# emonDCduo_v0_1.net
KiCad netlist of a schematic drawn in EAGLE
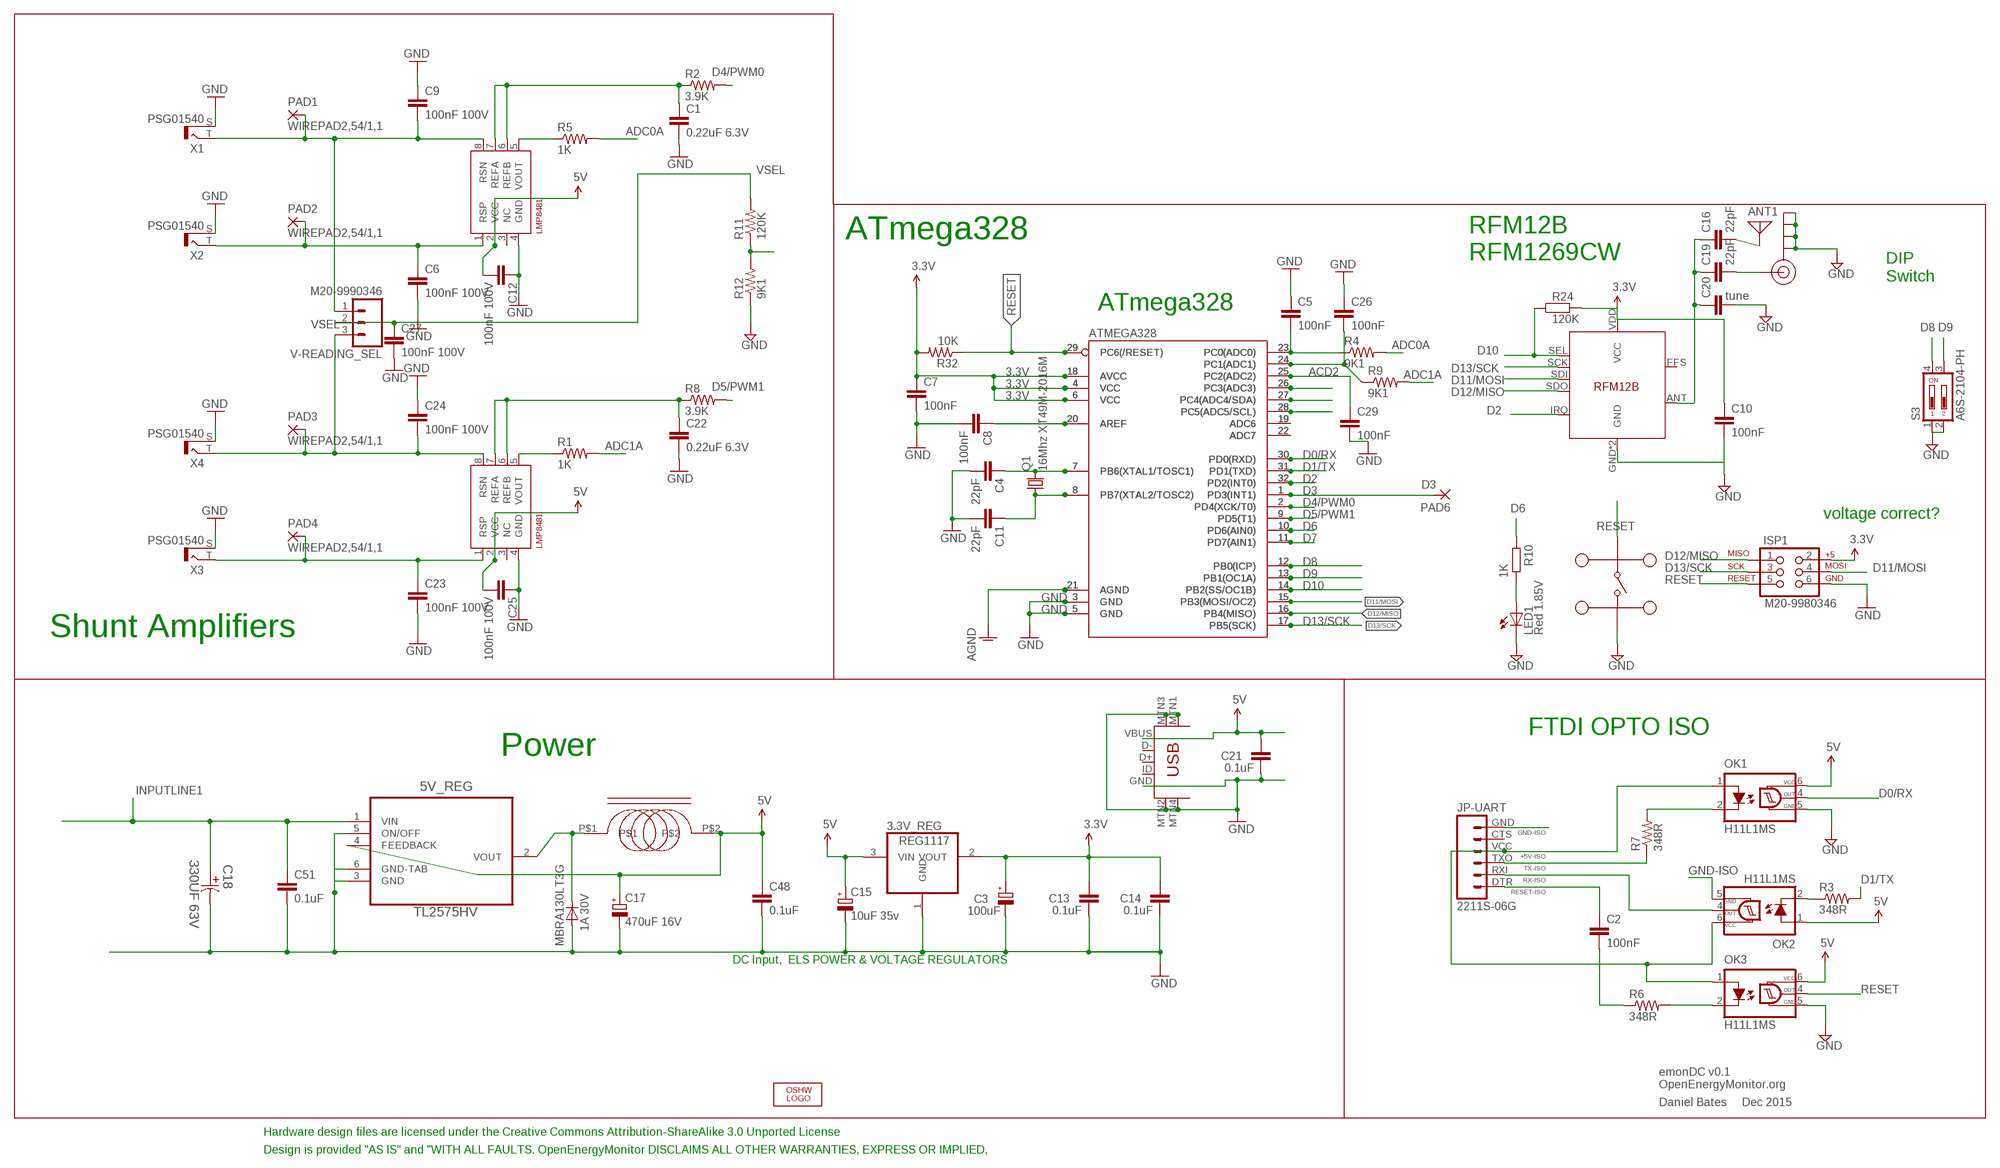
[diagram p0: schematic, sheet 1]

(export (version "E")
  (design (tool "Eeschema 10.0.6"))
  (components
    (comp (ref "3.3V_REG")
      (value "REG1117")
      (footprint "eagle-import:SOT223")
      (fields (field (name "MF") "TEXAS INSTRUMENTS"))
      (libsource (lib "eagle-import") (part "REG1117"))
    )
    (comp (ref "5V_REG")
      (value "TL2575HV")
      (footprint "eagle-import:TO-263")
      (fields (field (name "MF") "TEXAS INSTRUMENTS") (field (name "MPN") "LM2575HVS-15/NOPB"))
      (libsource (lib "eagle-import") (part "TL2575HV-05IKTTR"))
    )
    (comp (ref "ANT1")
      (value "ANTENNA")
      (footprint "eagle-import:PAD-01")
      (libsource (lib "eagle-import") (part "ANTENNA"))
    )
    (comp (ref "ATMEGA328")
      (value "ATMEGA168MLF")
      (footprint "eagle-import:MLF32")
      (fields (field (name "MF") "ATMEL") (field (name "MPN") "ATMEGA168-20MU"))
      (libsource (lib "eagle-import") (part "ATMEGA168MLF"))
    )
    (comp (ref "C1")
      (value "0.22uF 6.3V")
      (footprint "eagle-import:C0402K")
      (fields (field (name "MF") "AVX") (field (name "MPN") "04026D224KAT2A"))
      (libsource (lib "eagle-import") (part "C-EUC0402K"))
    )
    (comp (ref "C2")
      (value "100nF")
      (footprint "eagle-import:C0402K")
      (fields (field (name "MF") "WALSIN") (field (name "MPN") "0402X104K100CT"))
      (libsource (lib "eagle-import") (part "C-EUC0402K"))
    )
    (comp (ref "C3")
      (value "100uF")
      (footprint "eagle-import:153CLV-0605")
      (fields (field (name "MF") "NICHICON") (field (name "MPN") "UWX0J101MCL1GB"))
      (libsource (lib "eagle-import") (part "resistor_CPOL-EU153CLV-0605"))
    )
    (comp (ref "C4")
      (value "22pF")
      (footprint "eagle-import:C0603")
      (fields (field (name "MF") "YAGEO (PHYCOMP)") (field (name "MPN") "CC0402JRNPO9BN470"))
      (libsource (lib "eagle-import") (part "resistor_C-EUC0603"))
    )
    (comp (ref "C5")
      (value "100nF")
      (footprint "eagle-import:C0402K")
      (fields (field (name "MF") "WALSIN") (field (name "MPN") "0402X104K100CT"))
      (libsource (lib "eagle-import") (part "C-EUC0402K"))
    )
    (comp (ref "C6")
      (value "100nF 100V")
      (footprint "eagle-import:C0805K")
      (fields (field (name "MF") "AVX") (field (name "MPN") "08051C104K4Z2A"))
      (libsource (lib "eagle-import") (part "C-EUC0805K"))
    )
    (comp (ref "C7")
      (value "100nF")
      (footprint "eagle-import:C0402K")
      (fields (field (name "MF") "WALSIN") (field (name "MPN") "0402X104K100CT"))
      (libsource (lib "eagle-import") (part "C-EUC0402K"))
    )
    (comp (ref "C8")
      (value "100nF")
      (footprint "eagle-import:C0402K")
      (fields (field (name "MF") "WALSIN") (field (name "MPN") "0402X104K100CT"))
      (libsource (lib "eagle-import") (part "C-EUC0402K"))
    )
    (comp (ref "C9")
      (value "100nF 100V")
      (footprint "eagle-import:C0805K")
      (fields (field (name "MF") "AVX") (field (name "MPN") "08051C104K4Z2A"))
      (libsource (lib "eagle-import") (part "C-EUC0805K"))
    )
    (comp (ref "C10")
      (value "100nF")
      (footprint "eagle-import:C0402K")
      (fields (field (name "MF") "WALSIN") (field (name "MPN") "0402X104K100CT"))
      (libsource (lib "eagle-import") (part "C-EUC0402K"))
    )
    (comp (ref "C11")
      (value "22pF")
      (footprint "eagle-import:C0603")
      (fields (field (name "MF") "YAGEO (PHYCOMP)") (field (name "MPN") "CC0402JRNPO9BN470"))
      (libsource (lib "eagle-import") (part "resistor_C-EUC0603"))
    )
    (comp (ref "C12")
      (value "100nF 100V")
      (footprint "eagle-import:C0805K")
      (fields (field (name "MF") "AVX") (field (name "MPN") "08051C104K4Z2A"))
      (libsource (lib "eagle-import") (part "C-EUC0805K"))
    )
    (comp (ref "C13")
      (value "0.1uF")
      (footprint "eagle-import:C0805K")
      (fields (field (name "MF") "WALSIN") (field (name "MPN") "0805B104K160CT"))
      (libsource (lib "eagle-import") (part "C-EUC0805K"))
    )
    (comp (ref "C14")
      (value "0.1uF")
      (footprint "eagle-import:C0805K")
      (fields (field (name "MF") "WALSIN") (field (name "MPN") "0805B104K160CT"))
      (libsource (lib "eagle-import") (part "C-EUC0805K"))
    )
    (comp (ref "C15")
      (value "10uF 35v")
      (footprint "eagle-import:E1,8-4")
      (fields (field (name "MF") "AVX") (field (name "MPN") "TAJD106K035RNJ"))
      (libsource (lib "eagle-import") (part "CPOL-EUE1.8-4"))
    )
    (comp (ref "C16")
      (value "22pF")
      (footprint "eagle-import:C0603")
      (fields (field (name "MF") "YAGEO (PHYCOMP)") (field (name "MPN") "CC0402JRNPO9BN470"))
      (libsource (lib "eagle-import") (part "C-EUC0603"))
    )
    (comp (ref "C17")
      (value "470uF 16V")
      (footprint "eagle-import:E3,5-8")
      (fields (field (name "MF") "RUBYCON") (field (name "MPN") "16YXF470MEFC10X12.5"))
      (libsource (lib "eagle-import") (part "CPOL-EUE3.5-8"))
    )
    (comp (ref "C18")
      (value "330UF 63V")
      (footprint "eagle-import:CAPPR500-1000X2000")
      (fields
        (field (name "MPN") "ECA1JHG331")
        (field (name "TOLERANCE") "±20 %")
        (field (name "MF") "PANASONIC ELECTRONIC COMPONENTS")
        (field (name "OC_FARNELL") "unknown")
      )
      (libsource (lib "eagle-import") (part "ECA-D10XP51JHG331"))
    )
    (comp (ref "C19")
      (value "22pF")
      (footprint "eagle-import:C0603")
      (fields (field (name "MF") "YAGEO (PHYCOMP)") (field (name "MPN") "CC0402JRNPO9BN470"))
      (libsource (lib "eagle-import") (part "C-EUC0603"))
    )
    (comp (ref "C20")
      (value "tune")
      (footprint "eagle-import:C0603")
      (libsource (lib "eagle-import") (part "C-EUC0603"))
    )
    (comp (ref "C21")
      (value "0.1uF")
      (footprint "eagle-import:C0805K")
      (fields (field (name "MF") "WALSIN") (field (name "MPN") "0805B104K160CT"))
      (libsource (lib "eagle-import") (part "C-EUC0805K"))
    )
    (comp (ref "C22")
      (value "0.22uF 6.3V")
      (footprint "eagle-import:C0402K")
      (fields (field (name "MF") "AVX") (field (name "MPN") "04026D224KAT2A"))
      (libsource (lib "eagle-import") (part "C-EUC0402K"))
    )
    (comp (ref "C23")
      (value "100nF 100V")
      (footprint "eagle-import:C0805K")
      (fields (field (name "MF") "AVX") (field (name "MPN") "08051C104K4Z2A"))
      (libsource (lib "eagle-import") (part "C-EUC0805K"))
    )
    (comp (ref "C24")
      (value "100nF 100V")
      (footprint "eagle-import:C0805K")
      (fields (field (name "MF") "AVX") (field (name "MPN") "08051C104K4Z2A"))
      (libsource (lib "eagle-import") (part "C-EUC0805K"))
    )
    (comp (ref "C25")
      (value "100nF 100V")
      (footprint "eagle-import:C0805K")
      (fields (field (name "MF") "AVX") (field (name "MPN") "08051C104K4Z2A"))
      (libsource (lib "eagle-import") (part "C-EUC0805K"))
    )
    (comp (ref "C26")
      (value "100nF")
      (footprint "eagle-import:C0402K")
      (fields (field (name "MF") "WALSIN") (field (name "MPN") "0402X104K100CT"))
      (libsource (lib "eagle-import") (part "C-EUC0402K"))
    )
    (comp (ref "C27")
      (value "100nF 100V")
      (footprint "eagle-import:C0805K")
      (fields (field (name "MF") "AVX") (field (name "MPN") "08051C104K4Z2A"))
      (libsource (lib "eagle-import") (part "C-EUC0805K"))
    )
    (comp (ref "C29")
      (value "100nF")
      (footprint "eagle-import:C0402K")
      (fields (field (name "MF") "WALSIN") (field (name "MPN") "0402X104K100CT"))
      (libsource (lib "eagle-import") (part "C-EUC0402K"))
    )
    (comp (ref "C48")
      (value "0.1uF")
      (footprint "eagle-import:C0805K")
      (fields (field (name "MF") "WALSIN") (field (name "MPN") "0805B104K160CT"))
      (libsource (lib "eagle-import") (part "C-EUC0805K"))
    )
    (comp (ref "C51")
      (value "0.1uF")
      (footprint "eagle-import:C0805")
      (fields (field (name "MF") "WALSIN") (field (name "MPN") "0805B104K160CT"))
      (libsource (lib "eagle-import") (part "resistor_C-EUC0805"))
    )
    (comp (ref "D2")
      (value "MBRA130LT3G")
      (footprint "eagle-import:DO-214")
      (fields (field (name "MF") "ON SEMICONDUCTOR"))
      (libsource (lib "eagle-import") (part "MBRA130LT3G"))
    )
    (comp (ref "I1")
      (value "SRR0603-331KL")
      (footprint "eagle-import:SRR0603-331KL")
      (fields (field (name "MF") "BOURNS"))
      (libsource (lib "eagle-import") (part "SRR0603-331KL"))
    )
    (comp (ref "ISP1")
      (value "M20-9980346")
      (footprint "eagle-import:2X3")
      (fields (field (name "MF") "HARWIN"))
      (libsource (lib "eagle-import") (part "AVR_SPI_PRG_6PTH"))
    )
    (comp (ref "J$1")
      (value "SMA_EDGE")
      (footprint "eagle-import:SMA-EDGE")
      (libsource (lib "eagle-import") (part "SMA_EDGE"))
    )
    (comp (ref "JP-UART")
      (value "2211S-06G")
      (footprint "eagle-import:FTDI_BASIC")
      (fields (field (name "MF") "MULTICOMP"))
      (libsource (lib "eagle-import") (part "FTDI_BASICPTH"))
    )
    (comp (ref "LED1")
      (value "Red 1.85V")
      (footprint "eagle-import:CHIP-LED0805")
      (fields (field (name "MF") "ROHM") (field (name "MPN") "SML-211UTT86K"))
      (libsource (lib "eagle-import") (part "LEDCHIP-LED0805"))
    )
    (comp (ref "LMP2")
      (value "LMP8481SMCLMP8481")
      (footprint "eagle-import:S-PDSO-G08")
      (fields (field (name "MF") "TEXAS INSTRUMENTS") (field (name "MPN") "LMP8481MME-S/NOPB"))
      (libsource (lib "eagle-import") (part "LMP8481SMCLMP8481"))
    )
    (comp (ref "LMP8481")
      (value "LMP8481SMCLMP8481")
      (footprint "eagle-import:S-PDSO-G08")
      (fields (field (name "MF") "TEXAS INSTRUMENTS") (field (name "MPN") "LMP8481MME-S/NOPB"))
      (libsource (lib "eagle-import") (part "LMP8481SMCLMP8481"))
    )
    (comp (ref "LOGO1")
      (value "OSHW_LOGO_6MILX0200-NT")
      (footprint "eagle-import:OSHW_6X200_NOTEXT")
      (libsource (lib "eagle-import") (part "OSHW_LOGO_6MILX0200-NT"))
    )
    (comp (ref "OK1")
      (value "H11L1MS")
      (footprint "eagle-import:DIL6-SMD")
      (libsource (lib "eagle-import") (part "H11LMS1"))
    )
    (comp (ref "OK2")
      (value "H11L1MS")
      (footprint "eagle-import:DIL6-SMD")
      (libsource (lib "eagle-import") (part "H11LMS1"))
    )
    (comp (ref "OK3")
      (value "H11L1MS")
      (footprint "eagle-import:DIL6-SMD")
      (libsource (lib "eagle-import") (part "H11LMS1"))
    )
    (comp (ref "PAD1")
      (value "WIREPAD2,54/1,1")
      (footprint "eagle-import:2,54_1,1")
      (libsource (lib "eagle-import") (part "WIREPAD2,54/1,1"))
    )
    (comp (ref "PAD2")
      (value "WIREPAD2,54/1,1")
      (footprint "eagle-import:2,54_1,1")
      (libsource (lib "eagle-import") (part "WIREPAD2,54/1,1"))
    )
    (comp (ref "PAD3")
      (value "WIREPAD2,54/1,1")
      (footprint "eagle-import:2,54_1,1")
      (libsource (lib "eagle-import") (part "WIREPAD2,54/1,1"))
    )
    (comp (ref "PAD4")
      (value "WIREPAD2,54/1,1")
      (footprint "eagle-import:2,54_1,1")
      (libsource (lib "eagle-import") (part "WIREPAD2,54/1,1"))
    )
    (comp (ref "PAD6")
      (value "WIREPAD2,54/1,1")
      (footprint "eagle-import:2,54_1,1")
      (libsource (lib "eagle-import") (part "WIREPAD2,54/1,1"))
    )
    (comp (ref "Q1")
      (value "16Mhz XT49M-2016M")
      (footprint "eagle-import:HC49UP")
      (fields
        (field (name "MF") "VISHAY")
        (field (name "MPN") "XT49M-2016M")
        (field (name "OC_FARNELL") "1469641")
      )
      (libsource (lib "eagle-import") (part "CRYSTALHC49UP"))
    )
    (comp (ref "R1")
      (value "1K")
      (footprint "eagle-import:R0603")
      (fields (field (name "MF") "MULTICOMP") (field (name "MPN") "MC0063W060351K"))
      (libsource (lib "eagle-import") (part "R-US_R0603"))
    )
    (comp (ref "R2")
      (value "3.9K")
      (footprint "eagle-import:R0603")
      (fields (field (name "MF") "VISHAY") (field (name "MPN") "CRCW06039K09FKEA"))
      (libsource (lib "eagle-import") (part "R-US_R0603"))
    )
    (comp (ref "R3")
      (value "348R")
      (footprint "eagle-import:R0603")
      (fields (field (name "MF") "MULTICOMP") (field (name "MPN") "MC0063W06031348R"))
      (libsource (lib "eagle-import") (part "R-US_R0603"))
    )
    (comp (ref "R4")
      (value "9K1")
      (footprint "eagle-import:R0603")
      (fields (field (name "MF") "MULTICOMP") (field (name "MPN") "MC01W080559K1"))
      (libsource (lib "eagle-import") (part "R-US_R0603"))
    )
    (comp (ref "R5")
      (value "1K")
      (footprint "eagle-import:R0603")
      (fields (field (name "MF") "MULTICOMP") (field (name "MPN") "MC0063W060351K"))
      (libsource (lib "eagle-import") (part "R-US_R0603"))
    )
    (comp (ref "R6")
      (value "348R")
      (footprint "eagle-import:R0603")
      (fields (field (name "MF") "MULTICOMP") (field (name "MPN") "MC0063W06031348R"))
      (libsource (lib "eagle-import") (part "R-US_R0603"))
    )
    (comp (ref "R7")
      (value "348R")
      (footprint "eagle-import:R0603")
      (fields (field (name "MF") "MULTICOMP") (field (name "MPN") "MC0063W06031348R"))
      (libsource (lib "eagle-import") (part "R-US_R0603"))
    )
    (comp (ref "R8")
      (value "3.9K")
      (footprint "eagle-import:R0603")
      (fields (field (name "MF") "VISHAY") (field (name "MPN") "CRCW06039K09FKEA"))
      (libsource (lib "eagle-import") (part "R-US_R0603"))
    )
    (comp (ref "R9")
      (value "9K1")
      (footprint "eagle-import:R0603")
      (fields (field (name "MF") "MULTICOMP") (field (name "MPN") "MC01W080559K1"))
      (libsource (lib "eagle-import") (part "R-US_R0603"))
    )
    (comp (ref "R10")
      (value "1K")
      (footprint "eagle-import:R0603")
      (fields (field (name "MF") "MULTICOMP") (field (name "MPN") "MC0063W060351K"))
      (libsource (lib "eagle-import") (part "R-EU_R0603"))
    )
    (comp (ref "R11")
      (value "120K")
      (footprint "eagle-import:R0603")
      (fields (field (name "MF") "MULTICOMP") (field (name "MPN") "MC01W080559K1"))
      (libsource (lib "eagle-import") (part "R-US_R0603"))
    )
    (comp (ref "R12")
      (value "9K1")
      (footprint "eagle-import:R0603")
      (fields (field (name "MF") "MULTICOMP") (field (name "MPN") "MC01W080559K1"))
      (libsource (lib "eagle-import") (part "R-US_R0603"))
    )
    (comp (ref "R24")
      (value "120K")
      (footprint "eagle-import:R0603")
      (fields (field (name "MF") "YAGEO (PHYCOMP)") (field (name "MPN") "RC0603FR-07120KL"))
      (libsource (lib "eagle-import") (part "R-EU_R0603"))
    )
    (comp (ref "R32")
      (value "10K")
      (footprint "eagle-import:R0603")
      (fields (field (name "MF") "MULTICOMP") (field (name "MPN") "MC0063W0603510K"))
      (libsource (lib "eagle-import") (part "R-US_R0603"))
    )
    (comp (ref "RF")
      (value "RFM12B")
      (footprint "eagle-import:RFM12B")
      (libsource (lib "eagle-import") (part "RFM12B"))
    )
    (comp (ref "S3")
      (value "A6S-2104-PH")
      (footprint "eagle-import:DIP_SWITCH_SMT")
      (fields (field (name "MF") "OMRON ELECTRONIC COMPONENTS") (field (name "MPN") "A6S2104H"))
      (libsource (lib "eagle-import") (part "2_SMT_DIP_SWITCH"))
    )
    (comp (ref "U$1")
      (value "MC32882")
      (footprint "eagle-import:SWITCH_TACT_MULTICOMP")
      (libsource (lib "eagle-import") (part "MC32882"))
    )
    (comp (ref "U1_TQFP")
      (value "ATMEGA328P")
      (footprint "eagle-import:TQFP32-08")
      (fields (field (name "MF") "ATMEL") (field (name "MPN") "ATMEGA328-AU"))
      (libsource (lib "eagle-import") (part "ATMEGA328_SMT"))
    )
    (comp (ref "USB")
      (value "MUSB-05-S-B-SM-A")
      (footprint "eagle-import:USB-MINIB-CISECO")
      (fields (field (name "MF") "MOLEX") (field (name "MPN") "67503-1020"))
      (libsource (lib "eagle-import") (part "USB-MINIB-5PIN"))
    )
    (comp (ref "V-READING_SEL")
      (value "M20-9990346")
      (footprint "eagle-import:1X03_SMD_RA_FEMALE_NOWRITE")
      (fields (field (name "MF") "HARWIN"))
      (libsource (lib "eagle-import") (part "M03SMD_RA_FEMALE_NOWRITE"))
    )
    (comp (ref "X1")
      (value "PSG01540")
      (footprint "eagle-import:WBTOR1")
      (fields
        (field (name "MPN") "WBTOR 1 BLACK")
        (field (name "MF") "PRO SIGNAL")
        (field (name "MPN_1") "PSG01540")
        (field (name "OC_FARNELL") "1280698")
      )
      (libsource (lib "eagle-import") (part "WBTOR1"))
    )
    (comp (ref "X2")
      (value "PSG01540")
      (footprint "eagle-import:WBTOR1")
      (fields
        (field (name "MPN") "WBTOR 1 BLACK")
        (field (name "MF") "PRO SIGNAL")
        (field (name "MPN_1") "PSG01540")
        (field (name "OC_FARNELL") "1280698")
      )
      (libsource (lib "eagle-import") (part "WBTOR1"))
    )
    (comp (ref "X3")
      (value "PSG01540")
      (footprint "eagle-import:WBTOR1")
      (fields
        (field (name "MPN") "WBTOR 1 BLACK")
        (field (name "MF") "PRO SIGNAL")
        (field (name "MPN_1") "PSG01540")
        (field (name "OC_FARNELL") "1280698")
      )
      (libsource (lib "eagle-import") (part "WBTOR1"))
    )
    (comp (ref "X4")
      (value "PSG01540")
      (footprint "eagle-import:WBTOR1")
      (fields
        (field (name "MPN") "WBTOR 1 BLACK")
        (field (name "MF") "PRO SIGNAL")
        (field (name "MPN_1") "PSG01540")
        (field (name "OC_FARNELL") "1280698")
      )
      (libsource (lib "eagle-import") (part "WBTOR1"))
    )
  )
  (nets
    (net (code "1") (name "/+5V-ISO") (class "Default")
      (node (ref "JP-UART") (pin "VCC") (pinfunction "4_VCC") (pintype "passive"))
      (node (ref "OK1") (pin "1") (pinfunction "A_1") (pintype "passive"))
      (node (ref "OK2") (pin "6") (pinfunction "VCC_6") (pintype "power_in"))
      (node (ref "OK3") (pin "1") (pinfunction "A_1") (pintype "passive"))
    )
    (net (code "2") (name "/ACD2") (class "Default")
      (node (ref "ATMEGA328") (pin "25") (pinfunction "PC2(ADC2)_25") (pintype "bidirectional"))
      (node (ref "C29") (pin "1") (pinfunction "1_1") (pintype "passive"))
      (node (ref "R11") (pin "1") (pinfunction "1_1") (pintype "passive"))
      (node (ref "R12") (pin "2") (pinfunction "2_2") (pintype "passive"))
      (node (ref "U1_TQFP") (pin "25") (pinfunction "PC2(ADC2)_25") (pintype "bidirectional"))
    )
    (net (code "3") (name "/ADC0A") (class "Default")
      (node (ref "R4") (pin "2") (pinfunction "2_2") (pintype "passive"))
      (node (ref "R5") (pin "2") (pinfunction "2_2") (pintype "passive"))
    )
    (net (code "4") (name "/ADC1A") (class "Default")
      (node (ref "R1") (pin "2") (pinfunction "2_2") (pintype "passive"))
      (node (ref "R9") (pin "2") (pinfunction "2_2") (pintype "passive"))
    )
    (net (code "5") (name "/D0{slash}RX") (class "Default")
      (node (ref "ATMEGA328") (pin "30") (pinfunction "PD0(RXD)_30") (pintype "bidirectional"))
      (node (ref "OK1") (pin "4") (pinfunction "OUT_4") (pintype "output"))
      (node (ref "U1_TQFP") (pin "30") (pinfunction "PD0(RXD)_30") (pintype "bidirectional"))
    )
    (net (code "6") (name "/D1{slash}TX") (class "Default")
      (node (ref "ATMEGA328") (pin "31") (pinfunction "PD1(TXD)_31") (pintype "bidirectional"))
      (node (ref "R3") (pin "2") (pinfunction "2_2") (pintype "passive"))
      (node (ref "U1_TQFP") (pin "31") (pinfunction "PD1(TXD)_31") (pintype "bidirectional"))
    )
    (net (code "7") (name "/D2") (class "Default")
      (node (ref "ATMEGA328") (pin "32") (pinfunction "PD2(INT0)_32") (pintype "bidirectional"))
      (node (ref "RF") (pin "IRQ") (pinfunction "IRQ_IRQ") (pintype "open_collector"))
      (node (ref "U1_TQFP") (pin "32") (pinfunction "PD2(INT0)_32") (pintype "bidirectional"))
    )
    (net (code "8") (name "/D3") (class "Default")
      (node (ref "ATMEGA328") (pin "1") (pinfunction "PD3(INT1)_1") (pintype "bidirectional"))
      (node (ref "PAD6") (pin "1") (pinfunction "P_1") (pintype "passive"))
      (node (ref "U1_TQFP") (pin "1") (pinfunction "PD3(INT1)_1") (pintype "bidirectional"))
    )
    (net (code "9") (name "/D4{slash}PWM0") (class "Default")
      (node (ref "ATMEGA328") (pin "2") (pinfunction "PD4(XCK/T0)_2") (pintype "bidirectional"))
      (node (ref "R2") (pin "2") (pinfunction "2_2") (pintype "passive"))
      (node (ref "U1_TQFP") (pin "2") (pinfunction "PD4(XCK/T0)_2") (pintype "bidirectional"))
    )
    (net (code "10") (name "/D5{slash}PWM1") (class "Default")
      (node (ref "ATMEGA328") (pin "9") (pinfunction "PD5(T1)_9") (pintype "bidirectional"))
      (node (ref "R8") (pin "2") (pinfunction "2_2") (pintype "passive"))
      (node (ref "U1_TQFP") (pin "9") (pinfunction "PD5(T1)_9") (pintype "bidirectional"))
    )
    (net (code "11") (name "/D6") (class "Default")
      (node (ref "ATMEGA328") (pin "10") (pinfunction "PD6(AIN0)_10") (pintype "bidirectional"))
      (node (ref "R10") (pin "2") (pinfunction "2_2") (pintype "passive"))
      (node (ref "U1_TQFP") (pin "10") (pinfunction "PD6(AIN0)_10") (pintype "bidirectional"))
    )
    (net (code "12") (name "/D7") (class "Default")
      (node (ref "ATMEGA328") (pin "11") (pinfunction "PD7(AIN1)_11") (pintype "bidirectional"))
      (node (ref "U1_TQFP") (pin "11") (pinfunction "PD7(AIN1)_11") (pintype "bidirectional"))
    )
    (net (code "13") (name "/D8") (class "Default")
      (node (ref "ATMEGA328") (pin "12") (pinfunction "PB0(ICP)_12") (pintype "bidirectional"))
      (node (ref "S3") (pin "4") (pinfunction "4_4") (pintype "passive"))
      (node (ref "U1_TQFP") (pin "12") (pinfunction "PB0(ICP)_12") (pintype "bidirectional"))
    )
    (net (code "14") (name "/D9") (class "Default")
      (node (ref "ATMEGA328") (pin "13") (pinfunction "PB1(OC1A)_13") (pintype "bidirectional"))
      (node (ref "S3") (pin "3") (pinfunction "3_3") (pintype "passive"))
      (node (ref "U1_TQFP") (pin "13") (pinfunction "PB1(OC1A)_13") (pintype "bidirectional"))
    )
    (net (code "15") (name "/D10") (class "Default")
      (node (ref "ATMEGA328") (pin "14") (pinfunction "PB2(SS/OC1B)_14") (pintype "bidirectional"))
      (node (ref "R24") (pin "1") (pinfunction "1_1") (pintype "passive"))
      (node (ref "RF") (pin "SEL") (pinfunction "SEL_SEL") (pintype "input"))
      (node (ref "U1_TQFP") (pin "14") (pinfunction "PB2(SS/OC1B)_14") (pintype "bidirectional"))
    )
    (net (code "16") (name "/GND-ISO") (class "Default")
      (node (ref "JP-UART") (pin "GND") (pinfunction "6_GND") (pintype "passive"))
      (node (ref "OK2") (pin "5") (pinfunction "GND_5") (pintype "power_in"))
    )
    (net (code "17") (name "/INPUTLINE1") (class "Default")
      (node (ref "5V_REG") (pin "1") (pinfunction "VIN_1") (pintype "input"))
      (node (ref "C18") (pin "1") (pinfunction "1_1") (pintype "passive"))
      (node (ref "C51") (pin "1") (pinfunction "1_1") (pintype "passive"))
      (node (ref "C9") (pin "2") (pinfunction "2_2") (pintype "passive"))
      (node (ref "LMP8481") (pin "8") (pinfunction "RSN_8") (pintype "bidirectional"))
      (node (ref "PAD1") (pin "1") (pinfunction "P_1") (pintype "passive"))
      (node (ref "V-READING_SEL") (pin "1") (pinfunction "1_1") (pintype "passive"))
      (node (ref "X1") (pin "T") (pinfunction "T_T") (pintype "passive"))
    )
    (net (code "18") (name "/RESET-ISO") (class "Default")
      (node (ref "C2") (pin "2") (pinfunction "2_2") (pintype "passive"))
      (node (ref "R6") (pin "1") (pinfunction "1_1") (pintype "passive"))
    )
    (net (code "19") (name "/RX-ISO") (class "Default")
      (node (ref "JP-UART") (pin "RXI") (pinfunction "2_RXI") (pintype "passive"))
      (node (ref "OK2") (pin "4") (pinfunction "OUT_4") (pintype "output"))
    )
    (net (code "20") (name "/TX-ISO") (class "Default")
      (node (ref "JP-UART") (pin "TXO") (pinfunction "3_TXO") (pintype "passive"))
      (node (ref "R7") (pin "1") (pinfunction "1_1") (pintype "passive"))
    )
    (net (code "21") (name "/VSEL") (class "Default")
      (node (ref "C27") (pin "1") (pinfunction "1_1") (pintype "passive"))
      (node (ref "R11") (pin "2") (pinfunction "2_2") (pintype "passive"))
      (node (ref "V-READING_SEL") (pin "2") (pinfunction "2_2") (pintype "passive"))
    )
    (net (code "22") (name "3.3V") (class "Default")
      (node (ref "3.3V_REG") (pin "2") (pinfunction "VOUT_2") (pintype "output"))
      (node (ref "ATMEGA328") (pin "18") (pinfunction "AVCC_18") (pintype "bidirectional"))
      (node (ref "ATMEGA328") (pin "4") (pinfunction "VCC_4") (pintype "bidirectional"))
      (node (ref "ATMEGA328") (pin "6") (pinfunction "VCC_6") (pintype "bidirectional"))
      (node (ref "C10") (pin "1") (pinfunction "1_1") (pintype "passive"))
      (node (ref "C13") (pin "1") (pinfunction "1_1") (pintype "passive"))
      (node (ref "C14") (pin "1") (pinfunction "1_1") (pintype "passive"))
      (node (ref "C3") (pin "+") (pinfunction "+_+") (pintype "passive"))
      (node (ref "C7") (pin "1") (pinfunction "1_1") (pintype "passive"))
      (node (ref "ISP1") (pin "2") (pinfunction "2_2") (pintype "passive"))
      (node (ref "R24") (pin "2") (pinfunction "2_2") (pintype "passive"))
      (node (ref "R32") (pin "2") (pinfunction "2_2") (pintype "passive"))
      (node (ref "RF") (pin "VDD") (pinfunction "VCC_VDD") (pintype "power_in"))
      (node (ref "U1_TQFP") (pin "18") (pinfunction "AVCC_18") (pintype "bidirectional"))
      (node (ref "U1_TQFP") (pin "4") (pinfunction "VCC_4") (pintype "bidirectional"))
      (node (ref "U1_TQFP") (pin "6") (pinfunction "VCC_6") (pintype "bidirectional"))
    )
    (net (code "23") (name "5V") (class "Default")
      (node (ref "3.3V_REG") (pin "3") (pinfunction "VIN_3") (pintype "input"))
      (node (ref "5V_REG") (pin "4") (pinfunction "FEEDBACK_4") (pintype "input"))
      (node (ref "C12") (pin "2") (pinfunction "2_2") (pintype "passive"))
      (node (ref "C15") (pin "+") (pinfunction "+_+") (pintype "passive"))
      (node (ref "C17") (pin "+") (pinfunction "+_+") (pintype "passive"))
      (node (ref "C21") (pin "1") (pinfunction "1_1") (pintype "passive"))
      (node (ref "C25") (pin "2") (pinfunction "2_2") (pintype "passive"))
      (node (ref "C48") (pin "1") (pinfunction "1_1") (pintype "passive"))
      (node (ref "I1") (pin "P$2") (pinfunction "P$2_P$2") (pintype "bidirectional"))
      (node (ref "LMP2") (pin "2") (pinfunction "VCC_2") (pintype "bidirectional"))
      (node (ref "LMP8481") (pin "2") (pinfunction "VCC_2") (pintype "bidirectional"))
      (node (ref "OK1") (pin "6") (pinfunction "VCC_6") (pintype "power_in"))
      (node (ref "OK2") (pin "1") (pinfunction "A_1") (pintype "passive"))
      (node (ref "OK3") (pin "6") (pinfunction "VCC_6") (pintype "power_in"))
      (node (ref "USB") (pin "VBUS") (pinfunction "VBUS_VBUS") (pintype "bidirectional"))
    )
    (net (code "24") (name "AGND") (class "Default")
      (node (ref "ATMEGA328") (pin "21") (pinfunction "AGND_21") (pintype "bidirectional"))
      (node (ref "U1_TQFP") (pin "21") (pinfunction "AGND_21") (pintype "bidirectional"))
    )
    (net (code "25") (name "D11{slash}MOSI") (class "Default")
      (node (ref "ATMEGA328") (pin "15") (pinfunction "PB3(MOSI/OC2)_15") (pintype "bidirectional"))
      (node (ref "ISP1") (pin "4") (pinfunction "4_4") (pintype "passive"))
      (node (ref "RF") (pin "SDI") (pinfunction "SDI_SDI") (pintype "input"))
      (node (ref "U1_TQFP") (pin "15") (pinfunction "PB3(MOSI/OC2)_15") (pintype "bidirectional"))
    )
    (net (code "26") (name "D12{slash}MISO") (class "Default")
      (node (ref "ATMEGA328") (pin "16") (pinfunction "PB4(MISO)_16") (pintype "bidirectional"))
      (node (ref "ISP1") (pin "1") (pinfunction "1_1") (pintype "passive"))
      (node (ref "RF") (pin "SDO") (pinfunction "SDO_SDO") (pintype "output"))
      (node (ref "U1_TQFP") (pin "16") (pinfunction "PB4(MISO)_16") (pintype "bidirectional"))
    )
    (net (code "27") (name "D13{slash}SCK") (class "Default")
      (node (ref "ATMEGA328") (pin "17") (pinfunction "PB5(SCK)_17") (pintype "bidirectional"))
      (node (ref "ISP1") (pin "3") (pinfunction "3_3") (pintype "passive"))
      (node (ref "RF") (pin "SCK") (pinfunction "SCK_SCK") (pintype "input"))
      (node (ref "U1_TQFP") (pin "17") (pinfunction "PB5(SCK)_17") (pintype "bidirectional"))
    )
    (net (code "28") (name "GND") (class "Default")
      (node (ref "3.3V_REG") (pin "1") (pinfunction "GND_1") (pintype "power_in"))
      (node (ref "5V_REG") (pin "3") (pinfunction "GND_3") (pintype "passive"))
      (node (ref "5V_REG") (pin "5") (pinfunction "ON/OFF_5") (pintype "input"))
      (node (ref "5V_REG") (pin "6") (pinfunction "GND-TAB_6") (pintype "passive"))
      (node (ref "ATMEGA328") (pin "3") (pinfunction "GND_3") (pintype "bidirectional"))
      (node (ref "ATMEGA328") (pin "5") (pinfunction "GND_5") (pintype "bidirectional"))
      (node (ref "C1") (pin "2") (pinfunction "2_2") (pintype "passive"))
      (node (ref "C10") (pin "2") (pinfunction "2_2") (pintype "passive"))
      (node (ref "C11") (pin "2") (pinfunction "2_2") (pintype "passive"))
      (node (ref "C12") (pin "1") (pinfunction "1_1") (pintype "passive"))
      (node (ref "C13") (pin "2") (pinfunction "2_2") (pintype "passive"))
      (node (ref "C14") (pin "2") (pinfunction "2_2") (pintype "passive"))
      (node (ref "C15") (pin "-") (pinfunction "-_-") (pintype "passive"))
      (node (ref "C17") (pin "-") (pinfunction "-_-") (pintype "passive"))
      (node (ref "C18") (pin "2") (pinfunction "2_2") (pintype "passive"))
      (node (ref "C20") (pin "2") (pinfunction "2_2") (pintype "passive"))
      (node (ref "C21") (pin "2") (pinfunction "2_2") (pintype "passive"))
      (node (ref "C22") (pin "2") (pinfunction "2_2") (pintype "passive"))
      (node (ref "C23") (pin "2") (pinfunction "2_2") (pintype "passive"))
      (node (ref "C24") (pin "1") (pinfunction "1_1") (pintype "passive"))
      (node (ref "C25") (pin "1") (pinfunction "1_1") (pintype "passive"))
      (node (ref "C26") (pin "1") (pinfunction "1_1") (pintype "passive"))
      (node (ref "C27") (pin "2") (pinfunction "2_2") (pintype "passive"))
      (node (ref "C29") (pin "2") (pinfunction "2_2") (pintype "passive"))
      (node (ref "C3") (pin "-") (pinfunction "-_-") (pintype "passive"))
      (node (ref "C4") (pin "2") (pinfunction "2_2") (pintype "passive"))
      (node (ref "C48") (pin "2") (pinfunction "2_2") (pintype "passive"))
      (node (ref "C5") (pin "1") (pinfunction "1_1") (pintype "passive"))
      (node (ref "C51") (pin "2") (pinfunction "2_2") (pintype "passive"))
      (node (ref "C6") (pin "2") (pinfunction "2_2") (pintype "passive"))
      (node (ref "C7") (pin "2") (pinfunction "2_2") (pintype "passive"))
      (node (ref "C8") (pin "2") (pinfunction "2_2") (pintype "passive"))
      (node (ref "C9") (pin "1") (pinfunction "1_1") (pintype "passive"))
      (node (ref "D2") (pin "P$2") (pinfunction "A_P$2") (pintype "passive"))
      (node (ref "ISP1") (pin "6") (pinfunction "6_6") (pintype "passive"))
      (node (ref "J$1") (pin "GND@0") (pinfunction "GND_GND@0") (pintype "bidirectional"))
      (node (ref "J$1") (pin "GND@1") (pinfunction "GND_GND@1") (pintype "bidirectional"))
      (node (ref "J$1") (pin "GND@2") (pinfunction "GND_GND@2") (pintype "bidirectional"))
      (node (ref "J$1") (pin "GND@3") (pinfunction "GND_GND@3") (pintype "bidirectional"))
      (node (ref "LED1") (pin "C") (pinfunction "C_C") (pintype "passive"))
      (node (ref "LMP2") (pin "4") (pinfunction "GND_4") (pintype "bidirectional"))
      (node (ref "LMP8481") (pin "4") (pinfunction "GND_4") (pintype "bidirectional"))
      (node (ref "OK1") (pin "5") (pinfunction "GND_5") (pintype "power_in"))
      (node (ref "OK3") (pin "5") (pinfunction "GND_5") (pintype "power_in"))
      (node (ref "R12") (pin "1") (pinfunction "1_1") (pintype "passive"))
      (node (ref "RF") (pin "GND") (pinfunction "GND_GND") (pintype "power_in"))
      (node (ref "RF") (pin "P$12") (pinfunction "GND_P$12") (pintype "power_in"))
      (node (ref "S3") (pin "1") (pinfunction "1_1") (pintype "passive"))
      (node (ref "S3") (pin "2") (pinfunction "2_2") (pintype "passive"))
      (node (ref "U$1") (pin "P$3") (pinfunction "P$2_P$3") (pintype "bidirectional"))
      (node (ref "U$1") (pin "P$4") (pinfunction "P$2_P$4") (pintype "bidirectional"))
      (node (ref "U1_TQFP") (pin "3") (pinfunction "GND_3") (pintype "bidirectional"))
      (node (ref "U1_TQFP") (pin "5") (pinfunction "GND_5") (pintype "bidirectional"))
      (node (ref "USB") (pin "GND") (pinfunction "GND_GND") (pintype "bidirectional"))
      (node (ref "USB") (pin "MTN1") (pinfunction "MTN2_MTN1") (pintype "bidirectional"))
      (node (ref "USB") (pin "MTN2") (pinfunction "MTN3_MTN2") (pintype "bidirectional"))
      (node (ref "USB") (pin "MTN3") (pinfunction "MTN1_MTN3") (pintype "bidirectional"))
      (node (ref "USB") (pin "MTN4") (pinfunction "MTN4_MTN4") (pintype "bidirectional"))
      (node (ref "X1") (pin "S") (pinfunction "S_S") (pintype "passive"))
      (node (ref "X2") (pin "S") (pinfunction "S_S") (pintype "passive"))
      (node (ref "X3") (pin "S") (pinfunction "S_S") (pintype "passive"))
      (node (ref "X4") (pin "S") (pinfunction "S_S") (pintype "passive"))
    )
    (net (code "29") (name "Net-(5V_REG-VOUT)") (class "Default")
      (node (ref "5V_REG") (pin "2") (pinfunction "VOUT_2") (pintype "output"))
      (node (ref "D2") (pin "P$1") (pinfunction "C_P$1") (pintype "passive"))
      (node (ref "I1") (pin "P$1") (pinfunction "P$1_P$1") (pintype "bidirectional"))
    )
    (net (code "30") (name "Net-(ANT1-Pad1)") (class "Default")
      (node (ref "ANT1") (pin "1") (pinfunction "1_1") (pintype "output"))
      (node (ref "C16") (pin "2") (pinfunction "2_2") (pintype "passive"))
    )
    (net (code "31") (name "Net-(ATMEGA328-ADC6)") (class "Default")
      (node (ref "ATMEGA328") (pin "19") (pinfunction "ADC6_19") (pintype "bidirectional"))
      (node (ref "U1_TQFP") (pin "19") (pinfunction "ADC6_19") (pintype "bidirectional"))
    )
    (net (code "32") (name "Net-(ATMEGA328-ADC7)") (class "Default")
      (node (ref "ATMEGA328") (pin "22") (pinfunction "ADC7_22") (pintype "bidirectional"))
      (node (ref "U1_TQFP") (pin "22") (pinfunction "ADC7_22") (pintype "bidirectional"))
    )
    (net (code "33") (name "Net-(ATMEGA328-AREF)") (class "Default")
      (node (ref "ATMEGA328") (pin "20") (pinfunction "AREF_20") (pintype "bidirectional"))
      (node (ref "C8") (pin "1") (pinfunction "1_1") (pintype "passive"))
      (node (ref "U1_TQFP") (pin "20") (pinfunction "AREF_20") (pintype "bidirectional"))
    )
    (net (code "34") (name "Net-(ATMEGA328-PB6(XTAL1{slash}TOSC1))") (class "Default")
      (node (ref "ATMEGA328") (pin "7") (pinfunction "PB6(XTAL1/TOSC1)_7") (pintype "bidirectional"))
      (node (ref "C4") (pin "1") (pinfunction "1_1") (pintype "passive"))
      (node (ref "Q1") (pin "2") (pinfunction "2_2") (pintype "passive"))
      (node (ref "U1_TQFP") (pin "7") (pinfunction "PB6(XTAL1/TOSC1)_7") (pintype "bidirectional"))
    )
    (net (code "35") (name "Net-(ATMEGA328-PB7(XTAL2{slash}TOSC2))") (class "Default")
      (node (ref "ATMEGA328") (pin "8") (pinfunction "PB7(XTAL2/TOSC2)_8") (pintype "bidirectional"))
      (node (ref "C11") (pin "1") (pinfunction "1_1") (pintype "passive"))
      (node (ref "Q1") (pin "1") (pinfunction "1_1") (pintype "passive"))
      (node (ref "U1_TQFP") (pin "8") (pinfunction "PB7(XTAL2/TOSC2)_8") (pintype "bidirectional"))
    )
    (net (code "36") (name "Net-(ATMEGA328-PC0(ADC0))") (class "Default")
      (node (ref "ATMEGA328") (pin "23") (pinfunction "PC0(ADC0)_23") (pintype "bidirectional"))
      (node (ref "C5") (pin "2") (pinfunction "2_2") (pintype "passive"))
      (node (ref "R4") (pin "1") (pinfunction "1_1") (pintype "passive"))
      (node (ref "U1_TQFP") (pin "23") (pinfunction "PC0(ADC0)_23") (pintype "bidirectional"))
    )
    (net (code "37") (name "Net-(ATMEGA328-PC1(ADC1))") (class "Default")
      (node (ref "ATMEGA328") (pin "24") (pinfunction "PC1(ADC1)_24") (pintype "bidirectional"))
      (node (ref "C26") (pin "2") (pinfunction "2_2") (pintype "passive"))
      (node (ref "R9") (pin "1") (pinfunction "1_1") (pintype "passive"))
      (node (ref "U1_TQFP") (pin "24") (pinfunction "PC1(ADC1)_24") (pintype "bidirectional"))
    )
    (net (code "38") (name "Net-(ATMEGA328-PC3(ADC3))") (class "Default")
      (node (ref "ATMEGA328") (pin "26") (pinfunction "PC3(ADC3)_26") (pintype "bidirectional"))
      (node (ref "U1_TQFP") (pin "26") (pinfunction "PC3(ADC3)_26") (pintype "bidirectional"))
    )
    (net (code "39") (name "Net-(ATMEGA328-PC4(ADC4{slash}SDA))") (class "Default")
      (node (ref "ATMEGA328") (pin "27") (pinfunction "PC4(ADC4/SDA)_27") (pintype "bidirectional"))
      (node (ref "U1_TQFP") (pin "27") (pinfunction "PC4(ADC4/SDA)_27") (pintype "bidirectional"))
    )
    (net (code "40") (name "Net-(ATMEGA328-PC5(ADC5{slash}SCL))") (class "Default")
      (node (ref "ATMEGA328") (pin "28") (pinfunction "PC5(ADC5/SCL)_28") (pintype "bidirectional"))
      (node (ref "U1_TQFP") (pin "28") (pinfunction "PC5(ADC5/SCL)_28") (pintype "bidirectional"))
    )
    (net (code "41") (name "Net-(C16-Pad1)") (class "Default")
      (node (ref "C16") (pin "1") (pinfunction "1_1") (pintype "passive"))
      (node (ref "C19") (pin "1") (pinfunction "1_1") (pintype "passive"))
      (node (ref "C20") (pin "1") (pinfunction "1_1") (pintype "passive"))
      (node (ref "RF") (pin "ANT") (pinfunction "ANT_ANT") (pintype "passive"))
    )
    (net (code "42") (name "Net-(J$1-SIGNAL)") (class "Default")
      (node (ref "C19") (pin "2") (pinfunction "2_2") (pintype "passive"))
      (node (ref "J$1") (pin "SIG") (pinfunction "SIGNAL_SIG") (pintype "bidirectional"))
    )
    (net (code "43") (name "Net-(JP-UART-1)") (class "Default")
      (node (ref "C2") (pin "1") (pinfunction "1_1") (pintype "passive"))
      (node (ref "JP-UART") (pin "DTR") (pinfunction "1_DTR") (pintype "passive"))
    )
    (net (code "44") (name "Net-(LED1-PadA)") (class "Default")
      (node (ref "LED1") (pin "A") (pinfunction "A_A") (pintype "passive"))
      (node (ref "R10") (pin "1") (pinfunction "1_1") (pintype "passive"))
    )
    (net (code "45") (name "Net-(LMP2-REFA)") (class "Default")
      (node (ref "C22") (pin "1") (pinfunction "1_1") (pintype "passive"))
      (node (ref "LMP2") (pin "6") (pinfunction "REFB_6") (pintype "bidirectional"))
      (node (ref "LMP2") (pin "7") (pinfunction "REFA_7") (pintype "bidirectional"))
      (node (ref "R8") (pin "1") (pinfunction "1_1") (pintype "passive"))
    )
    (net (code "46") (name "Net-(LMP2-RSN)") (class "Default")
      (node (ref "C24") (pin "2") (pinfunction "2_2") (pintype "passive"))
      (node (ref "LMP2") (pin "8") (pinfunction "RSN_8") (pintype "bidirectional"))
      (node (ref "PAD3") (pin "1") (pinfunction "P_1") (pintype "passive"))
      (node (ref "V-READING_SEL") (pin "3") (pinfunction "3_3") (pintype "passive"))
      (node (ref "X4") (pin "T") (pinfunction "T_T") (pintype "passive"))
    )
    (net (code "47") (name "Net-(LMP2-RSP)") (class "Default")
      (node (ref "C23") (pin "1") (pinfunction "1_1") (pintype "passive"))
      (node (ref "LMP2") (pin "1") (pinfunction "RSP_1") (pintype "bidirectional"))
      (node (ref "PAD4") (pin "1") (pinfunction "P_1") (pintype "passive"))
      (node (ref "X3") (pin "T") (pinfunction "T_T") (pintype "passive"))
    )
    (net (code "48") (name "Net-(LMP2-VOUT)") (class "Default")
      (node (ref "LMP2") (pin "5") (pinfunction "VOUT_5") (pintype "bidirectional"))
      (node (ref "R1") (pin "1") (pinfunction "1_1") (pintype "passive"))
    )
    (net (code "49") (name "Net-(LMP8481-REFA)") (class "Default")
      (node (ref "C1") (pin "1") (pinfunction "1_1") (pintype "passive"))
      (node (ref "LMP8481") (pin "6") (pinfunction "REFB_6") (pintype "bidirectional"))
      (node (ref "LMP8481") (pin "7") (pinfunction "REFA_7") (pintype "bidirectional"))
      (node (ref "R2") (pin "1") (pinfunction "1_1") (pintype "passive"))
    )
    (net (code "50") (name "Net-(LMP8481-RSP)") (class "Default")
      (node (ref "C6") (pin "1") (pinfunction "1_1") (pintype "passive"))
      (node (ref "LMP8481") (pin "1") (pinfunction "RSP_1") (pintype "bidirectional"))
      (node (ref "PAD2") (pin "1") (pinfunction "P_1") (pintype "passive"))
      (node (ref "X2") (pin "T") (pinfunction "T_T") (pintype "passive"))
    )
    (net (code "51") (name "Net-(LMP8481-VOUT)") (class "Default")
      (node (ref "LMP8481") (pin "5") (pinfunction "VOUT_5") (pintype "bidirectional"))
      (node (ref "R5") (pin "1") (pinfunction "1_1") (pintype "passive"))
    )
    (net (code "52") (name "Net-(OK1-C)") (class "Default")
      (node (ref "OK1") (pin "2") (pinfunction "C_2") (pintype "passive"))
      (node (ref "R7") (pin "2") (pinfunction "2_2") (pintype "passive"))
    )
    (net (code "53") (name "Net-(OK2-C)") (class "Default")
      (node (ref "OK2") (pin "2") (pinfunction "C_2") (pintype "passive"))
      (node (ref "R3") (pin "1") (pinfunction "1_1") (pintype "passive"))
    )
    (net (code "54") (name "Net-(OK3-C)") (class "Default")
      (node (ref "OK3") (pin "2") (pinfunction "C_2") (pintype "passive"))
      (node (ref "R6") (pin "2") (pinfunction "2_2") (pintype "passive"))
    )
    (net (code "55") (name "RESET") (class "Default")
      (node (ref "ATMEGA328") (pin "29") (pinfunction "PC6(/RESET)_29") (pintype "bidirectional"))
      (node (ref "ISP1") (pin "5") (pinfunction "5_5") (pintype "passive"))
      (node (ref "OK3") (pin "4") (pinfunction "OUT_4") (pintype "output"))
      (node (ref "R32") (pin "1") (pinfunction "1_1") (pintype "passive"))
      (node (ref "U$1") (pin "P$1") (pinfunction "P$1_P$1") (pintype "bidirectional"))
      (node (ref "U$1") (pin "P$2") (pinfunction "P$1_P$2") (pintype "bidirectional"))
      (node (ref "U1_TQFP") (pin "29") (pinfunction "PC6(/RESET)_29") (pintype "bidirectional"))
    )
    (net (code "56") (name "unconnected-(JP-UART-5-PadCTS)") (class "Default")
      (node (ref "JP-UART") (pin "CTS") (pinfunction "5_CTS") (pintype "passive"))
    )
    (net (code "57") (name "unconnected-(LMP2-NC-Pad3)") (class "Default")
      (node (ref "LMP2") (pin "3") (pinfunction "NC_3") (pintype "bidirectional"))
    )
    (net (code "58") (name "unconnected-(LMP8481-NC-Pad3)") (class "Default")
      (node (ref "LMP8481") (pin "3") (pinfunction "NC_3") (pintype "bidirectional"))
    )
    (net (code "59") (name "unconnected-(RF-PadFFS)") (class "Default")
      (node (ref "RF") (pin "FFS") (pinfunction "FFS_FFS") (pintype "bidirectional"))
    )
    (net (code "60") (name "unconnected-(USB-PadD+)") (class "Default")
      (node (ref "USB") (pin "D+") (pinfunction "D+_D+") (pintype "bidirectional"))
    )
    (net (code "61") (name "unconnected-(USB-PadD-)") (class "Default")
      (node (ref "USB") (pin "D-") (pinfunction "D-_D-") (pintype "bidirectional"))
    )
    (net (code "62") (name "unconnected-(USB-PadID)") (class "Default")
      (node (ref "USB") (pin "ID") (pinfunction "ID_ID") (pintype "bidirectional"))
    )
  )
)
